# Top.net
KiCad netlist of a schematic drawn in EAGLE
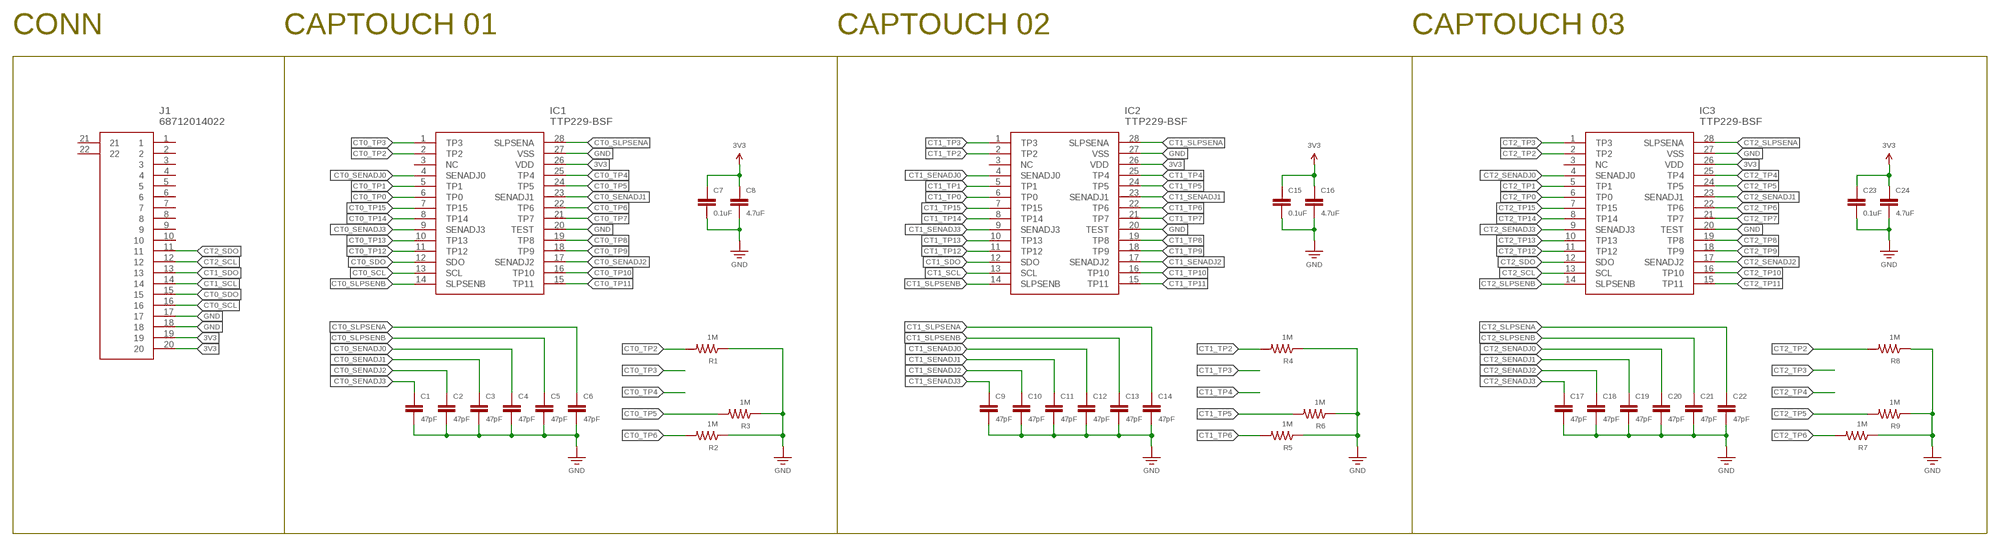
[diagram p0: schematic, sheet 1]

(export (version "E")
  (design (tool "Eeschema 10.0.6"))
  (components
    (comp (ref "C1")
      (value "47pF")
      (footprint "eagle-import:CAP-0603")
      (libsource (lib "eagle-import") (part "CAP-0603"))
    )
    (comp (ref "C2")
      (value "47pF")
      (footprint "eagle-import:CAP-0603")
      (libsource (lib "eagle-import") (part "CAP-0603"))
    )
    (comp (ref "C3")
      (value "47pF")
      (footprint "eagle-import:CAP-0603")
      (libsource (lib "eagle-import") (part "CAP-0603"))
    )
    (comp (ref "C4")
      (value "47pF")
      (footprint "eagle-import:CAP-0603")
      (libsource (lib "eagle-import") (part "CAP-0603"))
    )
    (comp (ref "C5")
      (value "47pF")
      (footprint "eagle-import:CAP-0603")
      (libsource (lib "eagle-import") (part "CAP-0603"))
    )
    (comp (ref "C6")
      (value "47pF")
      (footprint "eagle-import:CAP-0603")
      (libsource (lib "eagle-import") (part "CAP-0603"))
    )
    (comp (ref "C7")
      (value "0.1uF")
      (footprint "eagle-import:CAP-0603")
      (libsource (lib "eagle-import") (part "CAP-0603"))
    )
    (comp (ref "C8")
      (value "4.7uF")
      (footprint "eagle-import:CAP-0603")
      (libsource (lib "eagle-import") (part "CAP-0603"))
    )
    (comp (ref "C9")
      (value "47pF")
      (footprint "eagle-import:CAP-0603")
      (libsource (lib "eagle-import") (part "CAP-0603"))
    )
    (comp (ref "C10")
      (value "47pF")
      (footprint "eagle-import:CAP-0603")
      (libsource (lib "eagle-import") (part "CAP-0603"))
    )
    (comp (ref "C11")
      (value "47pF")
      (footprint "eagle-import:CAP-0603")
      (libsource (lib "eagle-import") (part "CAP-0603"))
    )
    (comp (ref "C12")
      (value "47pF")
      (footprint "eagle-import:CAP-0603")
      (libsource (lib "eagle-import") (part "CAP-0603"))
    )
    (comp (ref "C13")
      (value "47pF")
      (footprint "eagle-import:CAP-0603")
      (libsource (lib "eagle-import") (part "CAP-0603"))
    )
    (comp (ref "C14")
      (value "47pF")
      (footprint "eagle-import:CAP-0603")
      (libsource (lib "eagle-import") (part "CAP-0603"))
    )
    (comp (ref "C15")
      (value "0.1uF")
      (footprint "eagle-import:CAP-0603")
      (libsource (lib "eagle-import") (part "CAP-0603"))
    )
    (comp (ref "C16")
      (value "4.7uF")
      (footprint "eagle-import:CAP-0603")
      (libsource (lib "eagle-import") (part "CAP-0603"))
    )
    (comp (ref "C17")
      (value "47pF")
      (footprint "eagle-import:CAP-0603")
      (libsource (lib "eagle-import") (part "CAP-0603"))
    )
    (comp (ref "C18")
      (value "47pF")
      (footprint "eagle-import:CAP-0603")
      (libsource (lib "eagle-import") (part "CAP-0603"))
    )
    (comp (ref "C19")
      (value "47pF")
      (footprint "eagle-import:CAP-0603")
      (libsource (lib "eagle-import") (part "CAP-0603"))
    )
    (comp (ref "C20")
      (value "47pF")
      (footprint "eagle-import:CAP-0603")
      (libsource (lib "eagle-import") (part "CAP-0603"))
    )
    (comp (ref "C21")
      (value "47pF")
      (footprint "eagle-import:CAP-0603")
      (libsource (lib "eagle-import") (part "CAP-0603"))
    )
    (comp (ref "C22")
      (value "47pF")
      (footprint "eagle-import:CAP-0603")
      (libsource (lib "eagle-import") (part "CAP-0603"))
    )
    (comp (ref "C23")
      (value "0.1uF")
      (footprint "eagle-import:CAP-0603")
      (libsource (lib "eagle-import") (part "CAP-0603"))
    )
    (comp (ref "C24")
      (value "4.7uF")
      (footprint "eagle-import:CAP-0603")
      (libsource (lib "eagle-import") (part "CAP-0603"))
    )
    (comp (ref "IC1")
      (value "TTP229-BSF")
      (footprint "eagle-import:SOP64P600X175-28N")
      (libsource (lib "eagle-import") (part "TTP229-BSF"))
    )
    (comp (ref "IC2")
      (value "TTP229-BSF")
      (footprint "eagle-import:SOP64P600X175-28N")
      (libsource (lib "eagle-import") (part "TTP229-BSF"))
    )
    (comp (ref "IC3")
      (value "TTP229-BSF")
      (footprint "eagle-import:SOP64P600X175-28N")
      (libsource (lib "eagle-import") (part "TTP229-BSF"))
    )
    (comp (ref "J1")
      (value "68712014022")
      (footprint "eagle-import:68712014022")
      (fields (field (name "MOUSER_PART_NUMBER") "710-68712014022"))
      (libsource (lib "eagle-import") (part "68712014022"))
    )
    (comp (ref "R1")
      (value "1M")
      (footprint "eagle-import:RES-0603")
      (libsource (lib "eagle-import") (part "RES-0603"))
    )
    (comp (ref "R2")
      (value "1M")
      (footprint "eagle-import:RES-0603")
      (libsource (lib "eagle-import") (part "RES-0603"))
    )
    (comp (ref "R3")
      (value "1M")
      (footprint "eagle-import:RES-0603")
      (libsource (lib "eagle-import") (part "RES-0603"))
    )
    (comp (ref "R4")
      (value "1M")
      (footprint "eagle-import:RES-0603")
      (libsource (lib "eagle-import") (part "RES-0603"))
    )
    (comp (ref "R5")
      (value "1M")
      (footprint "eagle-import:RES-0603")
      (libsource (lib "eagle-import") (part "RES-0603"))
    )
    (comp (ref "R6")
      (value "1M")
      (footprint "eagle-import:RES-0603")
      (libsource (lib "eagle-import") (part "RES-0603"))
    )
    (comp (ref "R7")
      (value "1M")
      (footprint "eagle-import:RES-0603")
      (libsource (lib "eagle-import") (part "RES-0603"))
    )
    (comp (ref "R8")
      (value "1M")
      (footprint "eagle-import:RES-0603")
      (libsource (lib "eagle-import") (part "RES-0603"))
    )
    (comp (ref "R9")
      (value "1M")
      (footprint "eagle-import:RES-0603")
      (libsource (lib "eagle-import") (part "RES-0603"))
    )
  )
  (nets
    (net (code "1") (name "3V3") (class "Default")
      (node (ref "C15") (pin "P$1") (pinfunction "1_P$1") (pintype "passive"))
      (node (ref "C16") (pin "P$1") (pinfunction "1_P$1") (pintype "passive"))
      (node (ref "C23") (pin "P$1") (pinfunction "1_P$1") (pintype "passive"))
      (node (ref "C24") (pin "P$1") (pinfunction "1_P$1") (pintype "passive"))
      (node (ref "C7") (pin "P$1") (pinfunction "1_P$1") (pintype "passive"))
      (node (ref "C8") (pin "P$1") (pinfunction "1_P$1") (pintype "passive"))
      (node (ref "IC1") (pin "26") (pinfunction "VDD_26") (pintype "bidirectional"))
      (node (ref "IC2") (pin "26") (pinfunction "VDD_26") (pintype "bidirectional"))
      (node (ref "IC3") (pin "26") (pinfunction "VDD_26") (pintype "bidirectional"))
      (node (ref "J1") (pin "19") (pinfunction "19_19") (pintype "bidirectional"))
      (node (ref "J1") (pin "20") (pinfunction "20_20") (pintype "bidirectional"))
    )
    (net (code "2") (name "CT0_SCL") (class "Default")
      (node (ref "IC1") (pin "13") (pinfunction "SCL_13") (pintype "bidirectional"))
      (node (ref "J1") (pin "16") (pinfunction "16_16") (pintype "bidirectional"))
    )
    (net (code "3") (name "CT0_SDO") (class "Default")
      (node (ref "IC1") (pin "12") (pinfunction "SDO_12") (pintype "bidirectional"))
      (node (ref "J1") (pin "15") (pinfunction "15_15") (pintype "bidirectional"))
    )
    (net (code "4") (name "CT0_SENADJ0") (class "Default")
      (node (ref "C4") (pin "P$1") (pinfunction "1_P$1") (pintype "passive"))
      (node (ref "IC1") (pin "4") (pinfunction "SENADJ0_4") (pintype "bidirectional"))
    )
    (net (code "5") (name "CT0_SENADJ1") (class "Default")
      (node (ref "C3") (pin "P$1") (pinfunction "1_P$1") (pintype "passive"))
      (node (ref "IC1") (pin "23") (pinfunction "SENADJ1_23") (pintype "bidirectional"))
    )
    (net (code "6") (name "CT0_SENADJ2") (class "Default")
      (node (ref "C2") (pin "P$1") (pinfunction "1_P$1") (pintype "passive"))
      (node (ref "IC1") (pin "17") (pinfunction "SENADJ2_17") (pintype "bidirectional"))
    )
    (net (code "7") (name "CT0_SENADJ3") (class "Default")
      (node (ref "C1") (pin "P$1") (pinfunction "1_P$1") (pintype "passive"))
      (node (ref "IC1") (pin "9") (pinfunction "SENADJ3_9") (pintype "bidirectional"))
    )
    (net (code "8") (name "CT0_SLPSENA") (class "Default")
      (node (ref "C6") (pin "P$1") (pinfunction "1_P$1") (pintype "passive"))
      (node (ref "IC1") (pin "28") (pinfunction "SLPSENA_28") (pintype "bidirectional"))
    )
    (net (code "9") (name "CT0_SLPSENB") (class "Default")
      (node (ref "C5") (pin "P$1") (pinfunction "1_P$1") (pintype "passive"))
      (node (ref "IC1") (pin "14") (pinfunction "SLPSENB_14") (pintype "bidirectional"))
    )
    (net (code "10") (name "CT0_TP0") (class "Default")
      (node (ref "IC1") (pin "6") (pinfunction "TP0_6") (pintype "bidirectional"))
    )
    (net (code "11") (name "CT0_TP1") (class "Default")
      (node (ref "IC1") (pin "5") (pinfunction "TP1_5") (pintype "bidirectional"))
    )
    (net (code "12") (name "CT0_TP2") (class "Default")
      (node (ref "IC1") (pin "2") (pinfunction "TP2_2") (pintype "bidirectional"))
      (node (ref "R1") (pin "P$2") (pinfunction "2_P$2") (pintype "passive"))
    )
    (net (code "13") (name "CT0_TP3") (class "Default")
      (node (ref "IC1") (pin "1") (pinfunction "TP3_1") (pintype "bidirectional"))
    )
    (net (code "14") (name "CT0_TP4") (class "Default")
      (node (ref "IC1") (pin "25") (pinfunction "TP4_25") (pintype "bidirectional"))
    )
    (net (code "15") (name "CT0_TP5") (class "Default")
      (node (ref "IC1") (pin "24") (pinfunction "TP5_24") (pintype "bidirectional"))
      (node (ref "R3") (pin "P$2") (pinfunction "2_P$2") (pintype "passive"))
    )
    (net (code "16") (name "CT0_TP6") (class "Default")
      (node (ref "IC1") (pin "22") (pinfunction "TP6_22") (pintype "bidirectional"))
      (node (ref "R2") (pin "P$2") (pinfunction "2_P$2") (pintype "passive"))
    )
    (net (code "17") (name "CT0_TP7") (class "Default")
      (node (ref "IC1") (pin "21") (pinfunction "TP7_21") (pintype "bidirectional"))
    )
    (net (code "18") (name "CT0_TP8") (class "Default")
      (node (ref "IC1") (pin "19") (pinfunction "TP8_19") (pintype "bidirectional"))
    )
    (net (code "19") (name "CT0_TP9") (class "Default")
      (node (ref "IC1") (pin "18") (pinfunction "TP9_18") (pintype "bidirectional"))
    )
    (net (code "20") (name "CT0_TP10") (class "Default")
      (node (ref "IC1") (pin "16") (pinfunction "TP10_16") (pintype "bidirectional"))
    )
    (net (code "21") (name "CT0_TP11") (class "Default")
      (node (ref "IC1") (pin "15") (pinfunction "TP11_15") (pintype "bidirectional"))
    )
    (net (code "22") (name "CT0_TP12") (class "Default")
      (node (ref "IC1") (pin "11") (pinfunction "TP12_11") (pintype "bidirectional"))
    )
    (net (code "23") (name "CT0_TP13") (class "Default")
      (node (ref "IC1") (pin "10") (pinfunction "TP13_10") (pintype "bidirectional"))
    )
    (net (code "24") (name "CT0_TP14") (class "Default")
      (node (ref "IC1") (pin "8") (pinfunction "TP14_8") (pintype "bidirectional"))
    )
    (net (code "25") (name "CT0_TP15") (class "Default")
      (node (ref "IC1") (pin "7") (pinfunction "TP15_7") (pintype "bidirectional"))
    )
    (net (code "26") (name "CT1_SCL") (class "Default")
      (node (ref "IC2") (pin "13") (pinfunction "SCL_13") (pintype "bidirectional"))
      (node (ref "J1") (pin "14") (pinfunction "14_14") (pintype "bidirectional"))
    )
    (net (code "27") (name "CT1_SDO") (class "Default")
      (node (ref "IC2") (pin "12") (pinfunction "SDO_12") (pintype "bidirectional"))
      (node (ref "J1") (pin "13") (pinfunction "13_13") (pintype "bidirectional"))
    )
    (net (code "28") (name "CT1_SENADJ0") (class "Default")
      (node (ref "C12") (pin "P$1") (pinfunction "1_P$1") (pintype "passive"))
      (node (ref "IC2") (pin "4") (pinfunction "SENADJ0_4") (pintype "bidirectional"))
    )
    (net (code "29") (name "CT1_SENADJ1") (class "Default")
      (node (ref "C11") (pin "P$1") (pinfunction "1_P$1") (pintype "passive"))
      (node (ref "IC2") (pin "23") (pinfunction "SENADJ1_23") (pintype "bidirectional"))
    )
    (net (code "30") (name "CT1_SENADJ2") (class "Default")
      (node (ref "C10") (pin "P$1") (pinfunction "1_P$1") (pintype "passive"))
      (node (ref "IC2") (pin "17") (pinfunction "SENADJ2_17") (pintype "bidirectional"))
    )
    (net (code "31") (name "CT1_SENADJ3") (class "Default")
      (node (ref "C9") (pin "P$1") (pinfunction "1_P$1") (pintype "passive"))
      (node (ref "IC2") (pin "9") (pinfunction "SENADJ3_9") (pintype "bidirectional"))
    )
    (net (code "32") (name "CT1_SLPSENA") (class "Default")
      (node (ref "C14") (pin "P$1") (pinfunction "1_P$1") (pintype "passive"))
      (node (ref "IC2") (pin "28") (pinfunction "SLPSENA_28") (pintype "bidirectional"))
    )
    (net (code "33") (name "CT1_SLPSENB") (class "Default")
      (node (ref "C13") (pin "P$1") (pinfunction "1_P$1") (pintype "passive"))
      (node (ref "IC2") (pin "14") (pinfunction "SLPSENB_14") (pintype "bidirectional"))
    )
    (net (code "34") (name "CT1_TP0") (class "Default")
      (node (ref "IC2") (pin "6") (pinfunction "TP0_6") (pintype "bidirectional"))
    )
    (net (code "35") (name "CT1_TP1") (class "Default")
      (node (ref "IC2") (pin "5") (pinfunction "TP1_5") (pintype "bidirectional"))
    )
    (net (code "36") (name "CT1_TP2") (class "Default")
      (node (ref "IC2") (pin "2") (pinfunction "TP2_2") (pintype "bidirectional"))
      (node (ref "R4") (pin "P$2") (pinfunction "2_P$2") (pintype "passive"))
    )
    (net (code "37") (name "CT1_TP3") (class "Default")
      (node (ref "IC2") (pin "1") (pinfunction "TP3_1") (pintype "bidirectional"))
    )
    (net (code "38") (name "CT1_TP4") (class "Default")
      (node (ref "IC2") (pin "25") (pinfunction "TP4_25") (pintype "bidirectional"))
    )
    (net (code "39") (name "CT1_TP5") (class "Default")
      (node (ref "IC2") (pin "24") (pinfunction "TP5_24") (pintype "bidirectional"))
      (node (ref "R6") (pin "P$2") (pinfunction "2_P$2") (pintype "passive"))
    )
    (net (code "40") (name "CT1_TP6") (class "Default")
      (node (ref "IC2") (pin "22") (pinfunction "TP6_22") (pintype "bidirectional"))
      (node (ref "R5") (pin "P$2") (pinfunction "2_P$2") (pintype "passive"))
    )
    (net (code "41") (name "CT1_TP7") (class "Default")
      (node (ref "IC2") (pin "21") (pinfunction "TP7_21") (pintype "bidirectional"))
    )
    (net (code "42") (name "CT1_TP8") (class "Default")
      (node (ref "IC2") (pin "19") (pinfunction "TP8_19") (pintype "bidirectional"))
    )
    (net (code "43") (name "CT1_TP9") (class "Default")
      (node (ref "IC2") (pin "18") (pinfunction "TP9_18") (pintype "bidirectional"))
    )
    (net (code "44") (name "CT1_TP10") (class "Default")
      (node (ref "IC2") (pin "16") (pinfunction "TP10_16") (pintype "bidirectional"))
    )
    (net (code "45") (name "CT1_TP11") (class "Default")
      (node (ref "IC2") (pin "15") (pinfunction "TP11_15") (pintype "bidirectional"))
    )
    (net (code "46") (name "CT1_TP12") (class "Default")
      (node (ref "IC2") (pin "11") (pinfunction "TP12_11") (pintype "bidirectional"))
    )
    (net (code "47") (name "CT1_TP13") (class "Default")
      (node (ref "IC2") (pin "10") (pinfunction "TP13_10") (pintype "bidirectional"))
    )
    (net (code "48") (name "CT1_TP14") (class "Default")
      (node (ref "IC2") (pin "8") (pinfunction "TP14_8") (pintype "bidirectional"))
    )
    (net (code "49") (name "CT1_TP15") (class "Default")
      (node (ref "IC2") (pin "7") (pinfunction "TP15_7") (pintype "bidirectional"))
    )
    (net (code "50") (name "CT2_SCL") (class "Default")
      (node (ref "IC3") (pin "13") (pinfunction "SCL_13") (pintype "bidirectional"))
      (node (ref "J1") (pin "12") (pinfunction "12_12") (pintype "bidirectional"))
    )
    (net (code "51") (name "CT2_SDO") (class "Default")
      (node (ref "IC3") (pin "12") (pinfunction "SDO_12") (pintype "bidirectional"))
      (node (ref "J1") (pin "11") (pinfunction "11_11") (pintype "bidirectional"))
    )
    (net (code "52") (name "CT2_SENADJ0") (class "Default")
      (node (ref "C20") (pin "P$1") (pinfunction "1_P$1") (pintype "passive"))
      (node (ref "IC3") (pin "4") (pinfunction "SENADJ0_4") (pintype "bidirectional"))
    )
    (net (code "53") (name "CT2_SENADJ1") (class "Default")
      (node (ref "C19") (pin "P$1") (pinfunction "1_P$1") (pintype "passive"))
      (node (ref "IC3") (pin "23") (pinfunction "SENADJ1_23") (pintype "bidirectional"))
    )
    (net (code "54") (name "CT2_SENADJ2") (class "Default")
      (node (ref "C18") (pin "P$1") (pinfunction "1_P$1") (pintype "passive"))
      (node (ref "IC3") (pin "17") (pinfunction "SENADJ2_17") (pintype "bidirectional"))
    )
    (net (code "55") (name "CT2_SENADJ3") (class "Default")
      (node (ref "C17") (pin "P$1") (pinfunction "1_P$1") (pintype "passive"))
      (node (ref "IC3") (pin "9") (pinfunction "SENADJ3_9") (pintype "bidirectional"))
    )
    (net (code "56") (name "CT2_SLPSENA") (class "Default")
      (node (ref "C22") (pin "P$1") (pinfunction "1_P$1") (pintype "passive"))
      (node (ref "IC3") (pin "28") (pinfunction "SLPSENA_28") (pintype "bidirectional"))
    )
    (net (code "57") (name "CT2_SLPSENB") (class "Default")
      (node (ref "C21") (pin "P$1") (pinfunction "1_P$1") (pintype "passive"))
      (node (ref "IC3") (pin "14") (pinfunction "SLPSENB_14") (pintype "bidirectional"))
    )
    (net (code "58") (name "CT2_TP0") (class "Default")
      (node (ref "IC3") (pin "6") (pinfunction "TP0_6") (pintype "bidirectional"))
    )
    (net (code "59") (name "CT2_TP1") (class "Default")
      (node (ref "IC3") (pin "5") (pinfunction "TP1_5") (pintype "bidirectional"))
    )
    (net (code "60") (name "CT2_TP2") (class "Default")
      (node (ref "IC3") (pin "2") (pinfunction "TP2_2") (pintype "bidirectional"))
      (node (ref "R8") (pin "P$2") (pinfunction "2_P$2") (pintype "passive"))
    )
    (net (code "61") (name "CT2_TP3") (class "Default")
      (node (ref "IC3") (pin "1") (pinfunction "TP3_1") (pintype "bidirectional"))
    )
    (net (code "62") (name "CT2_TP4") (class "Default")
      (node (ref "IC3") (pin "25") (pinfunction "TP4_25") (pintype "bidirectional"))
    )
    (net (code "63") (name "CT2_TP5") (class "Default")
      (node (ref "IC3") (pin "24") (pinfunction "TP5_24") (pintype "bidirectional"))
      (node (ref "R9") (pin "P$2") (pinfunction "2_P$2") (pintype "passive"))
    )
    (net (code "64") (name "CT2_TP6") (class "Default")
      (node (ref "IC3") (pin "22") (pinfunction "TP6_22") (pintype "bidirectional"))
      (node (ref "R7") (pin "P$2") (pinfunction "2_P$2") (pintype "passive"))
    )
    (net (code "65") (name "CT2_TP7") (class "Default")
      (node (ref "IC3") (pin "21") (pinfunction "TP7_21") (pintype "bidirectional"))
    )
    (net (code "66") (name "CT2_TP8") (class "Default")
      (node (ref "IC3") (pin "19") (pinfunction "TP8_19") (pintype "bidirectional"))
    )
    (net (code "67") (name "CT2_TP9") (class "Default")
      (node (ref "IC3") (pin "18") (pinfunction "TP9_18") (pintype "bidirectional"))
    )
    (net (code "68") (name "CT2_TP10") (class "Default")
      (node (ref "IC3") (pin "16") (pinfunction "TP10_16") (pintype "bidirectional"))
    )
    (net (code "69") (name "CT2_TP11") (class "Default")
      (node (ref "IC3") (pin "15") (pinfunction "TP11_15") (pintype "bidirectional"))
    )
    (net (code "70") (name "CT2_TP12") (class "Default")
      (node (ref "IC3") (pin "11") (pinfunction "TP12_11") (pintype "bidirectional"))
    )
    (net (code "71") (name "CT2_TP13") (class "Default")
      (node (ref "IC3") (pin "10") (pinfunction "TP13_10") (pintype "bidirectional"))
    )
    (net (code "72") (name "CT2_TP14") (class "Default")
      (node (ref "IC3") (pin "8") (pinfunction "TP14_8") (pintype "bidirectional"))
    )
    (net (code "73") (name "CT2_TP15") (class "Default")
      (node (ref "IC3") (pin "7") (pinfunction "TP15_7") (pintype "bidirectional"))
    )
    (net (code "74") (name "GND") (class "Default")
      (node (ref "C1") (pin "P$2") (pinfunction "2_P$2") (pintype "passive"))
      (node (ref "C10") (pin "P$2") (pinfunction "2_P$2") (pintype "passive"))
      (node (ref "C11") (pin "P$2") (pinfunction "2_P$2") (pintype "passive"))
      (node (ref "C12") (pin "P$2") (pinfunction "2_P$2") (pintype "passive"))
      (node (ref "C13") (pin "P$2") (pinfunction "2_P$2") (pintype "passive"))
      (node (ref "C14") (pin "P$2") (pinfunction "2_P$2") (pintype "passive"))
      (node (ref "C15") (pin "P$2") (pinfunction "2_P$2") (pintype "passive"))
      (node (ref "C16") (pin "P$2") (pinfunction "2_P$2") (pintype "passive"))
      (node (ref "C17") (pin "P$2") (pinfunction "2_P$2") (pintype "passive"))
      (node (ref "C18") (pin "P$2") (pinfunction "2_P$2") (pintype "passive"))
      (node (ref "C19") (pin "P$2") (pinfunction "2_P$2") (pintype "passive"))
      (node (ref "C2") (pin "P$2") (pinfunction "2_P$2") (pintype "passive"))
      (node (ref "C20") (pin "P$2") (pinfunction "2_P$2") (pintype "passive"))
      (node (ref "C21") (pin "P$2") (pinfunction "2_P$2") (pintype "passive"))
      (node (ref "C22") (pin "P$2") (pinfunction "2_P$2") (pintype "passive"))
      (node (ref "C23") (pin "P$2") (pinfunction "2_P$2") (pintype "passive"))
      (node (ref "C24") (pin "P$2") (pinfunction "2_P$2") (pintype "passive"))
      (node (ref "C3") (pin "P$2") (pinfunction "2_P$2") (pintype "passive"))
      (node (ref "C4") (pin "P$2") (pinfunction "2_P$2") (pintype "passive"))
      (node (ref "C5") (pin "P$2") (pinfunction "2_P$2") (pintype "passive"))
      (node (ref "C6") (pin "P$2") (pinfunction "2_P$2") (pintype "passive"))
      (node (ref "C7") (pin "P$2") (pinfunction "2_P$2") (pintype "passive"))
      (node (ref "C8") (pin "P$2") (pinfunction "2_P$2") (pintype "passive"))
      (node (ref "C9") (pin "P$2") (pinfunction "2_P$2") (pintype "passive"))
      (node (ref "IC1") (pin "20") (pinfunction "TEST_20") (pintype "bidirectional"))
      (node (ref "IC1") (pin "27") (pinfunction "VSS_27") (pintype "bidirectional"))
      (node (ref "IC2") (pin "20") (pinfunction "TEST_20") (pintype "bidirectional"))
      (node (ref "IC2") (pin "27") (pinfunction "VSS_27") (pintype "bidirectional"))
      (node (ref "IC3") (pin "20") (pinfunction "TEST_20") (pintype "bidirectional"))
      (node (ref "IC3") (pin "27") (pinfunction "VSS_27") (pintype "bidirectional"))
      (node (ref "J1") (pin "17") (pinfunction "17_17") (pintype "bidirectional"))
      (node (ref "J1") (pin "18") (pinfunction "18_18") (pintype "bidirectional"))
      (node (ref "R1") (pin "P$1") (pinfunction "1_P$1") (pintype "passive"))
      (node (ref "R2") (pin "P$1") (pinfunction "1_P$1") (pintype "passive"))
      (node (ref "R3") (pin "P$1") (pinfunction "1_P$1") (pintype "passive"))
      (node (ref "R4") (pin "P$1") (pinfunction "1_P$1") (pintype "passive"))
      (node (ref "R5") (pin "P$1") (pinfunction "1_P$1") (pintype "passive"))
      (node (ref "R6") (pin "P$1") (pinfunction "1_P$1") (pintype "passive"))
      (node (ref "R7") (pin "P$1") (pinfunction "1_P$1") (pintype "passive"))
      (node (ref "R8") (pin "P$1") (pinfunction "1_P$1") (pintype "passive"))
      (node (ref "R9") (pin "P$1") (pinfunction "1_P$1") (pintype "passive"))
    )
    (net (code "75") (name "unconnected-(IC1-NC-Pad3)") (class "Default")
      (node (ref "IC1") (pin "3") (pinfunction "NC_3") (pintype "no_connect"))
    )
    (net (code "76") (name "unconnected-(IC2-NC-Pad3)") (class "Default")
      (node (ref "IC2") (pin "3") (pinfunction "NC_3") (pintype "no_connect"))
    )
    (net (code "77") (name "unconnected-(IC3-NC-Pad3)") (class "Default")
      (node (ref "IC3") (pin "3") (pinfunction "NC_3") (pintype "no_connect"))
    )
    (net (code "78") (name "unconnected-(J1-Pad1)") (class "Default")
      (node (ref "J1") (pin "1") (pinfunction "1_1") (pintype "bidirectional"))
    )
    (net (code "79") (name "unconnected-(J1-Pad2)") (class "Default")
      (node (ref "J1") (pin "2") (pinfunction "2_2") (pintype "bidirectional"))
    )
    (net (code "80") (name "unconnected-(J1-Pad3)") (class "Default")
      (node (ref "J1") (pin "3") (pinfunction "3_3") (pintype "bidirectional"))
    )
    (net (code "81") (name "unconnected-(J1-Pad4)") (class "Default")
      (node (ref "J1") (pin "4") (pinfunction "4_4") (pintype "bidirectional"))
    )
    (net (code "82") (name "unconnected-(J1-Pad5)") (class "Default")
      (node (ref "J1") (pin "5") (pinfunction "5_5") (pintype "bidirectional"))
    )
    (net (code "83") (name "unconnected-(J1-Pad6)") (class "Default")
      (node (ref "J1") (pin "6") (pinfunction "6_6") (pintype "bidirectional"))
    )
    (net (code "84") (name "unconnected-(J1-Pad7)") (class "Default")
      (node (ref "J1") (pin "7") (pinfunction "7_7") (pintype "bidirectional"))
    )
    (net (code "85") (name "unconnected-(J1-Pad8)") (class "Default")
      (node (ref "J1") (pin "8") (pinfunction "8_8") (pintype "bidirectional"))
    )
    (net (code "86") (name "unconnected-(J1-Pad9)") (class "Default")
      (node (ref "J1") (pin "9") (pinfunction "9_9") (pintype "bidirectional"))
    )
    (net (code "87") (name "unconnected-(J1-Pad10)") (class "Default")
      (node (ref "J1") (pin "10") (pinfunction "10_10") (pintype "bidirectional"))
    )
    (net (code "88") (name "unconnected-(J1-Pad21)") (class "Default")
      (node (ref "J1") (pin "21") (pinfunction "21_21") (pintype "bidirectional"))
    )
    (net (code "89") (name "unconnected-(J1-Pad22)") (class "Default")
      (node (ref "J1") (pin "22") (pinfunction "22_22") (pintype "bidirectional"))
    )
  )
)
